# SDLbeerlight0.net
KiCad netlist of a schematic drawn in EAGLE
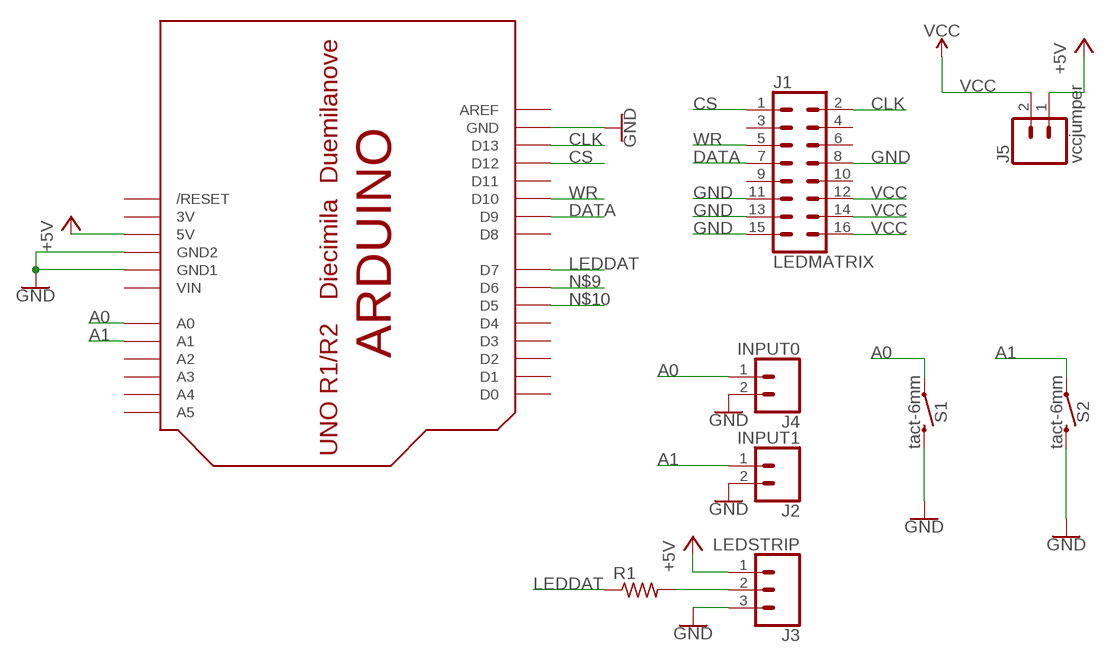
[diagram p0: schematic, sheet 1]

(export (version "E")
  (design (tool "Eeschema 10.0.6"))
  (components
    (comp (ref "J1")
      (value "LEDMATRIX")
      (footprint "eagle-import:2X8")
      (libsource (lib "eagle-import") (part "CONN_08X2"))
    )
    (comp (ref "J2")
      (value "INPUT1")
      (footprint "eagle-import:1X02_LONGPADS")
      (libsource (lib "eagle-import") (part "CONN_02PTH3"))
    )
    (comp (ref "J3")
      (value "LEDSTRIP")
      (footprint "eagle-import:1X03_LONGPADS")
      (libsource (lib "eagle-import") (part "CONN_03LONGPADS"))
    )
    (comp (ref "J4")
      (value "INPUT0")
      (footprint "eagle-import:1X02_LONGPADS")
      (libsource (lib "eagle-import") (part "CONN_02PTH3"))
    )
    (comp (ref "J5")
      (value "vccjumper")
      (footprint "eagle-import:1X02_LOCK_LONGPADS")
      (libsource (lib "eagle-import") (part "CONN_02LOCK_LONGPADS"))
    )
    (comp (ref "R1")
      (value "R-US_M0805")
      (footprint "eagle-import:M0805")
      (libsource (lib "eagle-import") (part "R-US_M0805"))
    )
    (comp (ref "S1")
      (value "tact-6mm")
      (footprint "eagle-import:TACTILE_SWITCH_PTH_6.0MM")
      (libsource (lib "eagle-import") (part "MOMENTARY-SWITCH-SPST-PTH-6.0MM"))
    )
    (comp (ref "S2")
      (value "tact-6mm")
      (footprint "eagle-import:TACTILE_SWITCH_PTH_6.0MM")
      (libsource (lib "eagle-import") (part "MOMENTARY-SWITCH-SPST-PTH-6.0MM"))
    )
    (comp (ref "U$2")
      (value "ARDUINOUNO")
      (footprint "eagle-import:ARDUINO")
      (libsource (lib "eagle-import") (part "ARDUINOUNO"))
    )
  )
  (nets
    (net (code "1") (name "+5V") (class "Default")
      (node (ref "J3") (pin "1") (pinfunction "1_1") (pintype "passive"))
      (node (ref "J5") (pin "1") (pinfunction "1_1") (pintype "passive"))
      (node (ref "U$2") (pin "5V") (pinfunction "5V_5V") (pintype "power_in"))
    )
    (net (code "2") (name "/3V") (class "Default")
      (node (ref "U$2") (pin "3V") (pinfunction "3V_3V") (pintype "power_in"))
    )
    (net (code "3") (name "/A0") (class "Default")
      (node (ref "J4") (pin "1") (pinfunction "1_1") (pintype "passive"))
      (node (ref "S1") (pin "1") (pinfunction "1_1") (pintype "passive"))
      (node (ref "U$2") (pin "A0") (pinfunction "A0_A0") (pintype "bidirectional"))
    )
    (net (code "4") (name "/A1") (class "Default")
      (node (ref "J2") (pin "1") (pinfunction "1_1") (pintype "passive"))
      (node (ref "S2") (pin "1") (pinfunction "1_1") (pintype "passive"))
      (node (ref "U$2") (pin "A1") (pinfunction "A1_A1") (pintype "bidirectional"))
    )
    (net (code "5") (name "/CLK") (class "Default")
      (node (ref "J1") (pin "2") (pinfunction "2_2") (pintype "passive"))
      (node (ref "U$2") (pin "D13") (pinfunction "D13_D13") (pintype "bidirectional"))
    )
    (net (code "6") (name "/CS") (class "Default")
      (node (ref "J1") (pin "1") (pinfunction "1_1") (pintype "passive"))
      (node (ref "U$2") (pin "D12") (pinfunction "D12_D12") (pintype "bidirectional"))
    )
    (net (code "7") (name "/DATA") (class "Default")
      (node (ref "J1") (pin "7") (pinfunction "7_7") (pintype "passive"))
      (node (ref "U$2") (pin "D9") (pinfunction "D9_D9") (pintype "bidirectional"))
    )
    (net (code "8") (name "/LEDDAT") (class "Default")
      (node (ref "R1") (pin "1") (pinfunction "1_1") (pintype "passive"))
      (node (ref "U$2") (pin "D7") (pinfunction "D7_D7") (pintype "bidirectional"))
    )
    (net (code "9") (name "/N$9") (class "Default")
      (node (ref "U$2") (pin "D6") (pinfunction "D6_D6") (pintype "bidirectional"))
    )
    (net (code "10") (name "/N$10") (class "Default")
      (node (ref "U$2") (pin "D5") (pinfunction "D5_D5") (pintype "bidirectional"))
    )
    (net (code "11") (name "/VIN") (class "Default")
      (node (ref "U$2") (pin "VIN") (pinfunction "VIN_VIN") (pintype "power_in"))
    )
    (net (code "12") (name "/WR") (class "Default")
      (node (ref "J1") (pin "5") (pinfunction "5_5") (pintype "passive"))
      (node (ref "U$2") (pin "D10") (pinfunction "D10_D10") (pintype "bidirectional"))
    )
    (net (code "13") (name "GND") (class "Default")
      (node (ref "J1") (pin "11") (pinfunction "11_11") (pintype "passive"))
      (node (ref "J1") (pin "13") (pinfunction "13_13") (pintype "passive"))
      (node (ref "J1") (pin "15") (pinfunction "15_15") (pintype "passive"))
      (node (ref "J1") (pin "8") (pinfunction "8_8") (pintype "passive"))
      (node (ref "J2") (pin "2") (pinfunction "2_2") (pintype "passive"))
      (node (ref "J3") (pin "3") (pinfunction "3_3") (pintype "passive"))
      (node (ref "J4") (pin "2") (pinfunction "2_2") (pintype "passive"))
      (node (ref "S1") (pin "3") (pinfunction "2_3") (pintype "passive"))
      (node (ref "S2") (pin "3") (pinfunction "2_3") (pintype "passive"))
      (node (ref "U$2") (pin "GND") (pinfunction "GND_GND") (pintype "power_in"))
      (node (ref "U$2") (pin "GND1") (pinfunction "GND1_GND1") (pintype "power_in"))
      (node (ref "U$2") (pin "GND2") (pinfunction "GND2_GND2") (pintype "power_in"))
    )
    (net (code "14") (name "Net-(J3-Pad2)") (class "Default")
      (node (ref "J3") (pin "2") (pinfunction "2_2") (pintype "passive"))
      (node (ref "R1") (pin "2") (pinfunction "2_2") (pintype "passive"))
    )
    (net (code "15") (name "VCC") (class "Default")
      (node (ref "J1") (pin "12") (pinfunction "12_12") (pintype "passive"))
      (node (ref "J1") (pin "14") (pinfunction "14_14") (pintype "passive"))
      (node (ref "J1") (pin "16") (pinfunction "16_16") (pintype "passive"))
      (node (ref "J5") (pin "2") (pinfunction "2_2") (pintype "passive"))
    )
    (net (code "16") (name "unconnected-(J1-Pad3)") (class "Default")
      (node (ref "J1") (pin "3") (pinfunction "3_3") (pintype "passive"))
    )
    (net (code "17") (name "unconnected-(J1-Pad4)") (class "Default")
      (node (ref "J1") (pin "4") (pinfunction "4_4") (pintype "passive"))
    )
    (net (code "18") (name "unconnected-(J1-Pad6)") (class "Default")
      (node (ref "J1") (pin "6") (pinfunction "6_6") (pintype "passive"))
    )
    (net (code "19") (name "unconnected-(J1-Pad9)") (class "Default")
      (node (ref "J1") (pin "9") (pinfunction "9_9") (pintype "passive"))
    )
    (net (code "20") (name "unconnected-(J1-Pad10)") (class "Default")
      (node (ref "J1") (pin "10") (pinfunction "10_10") (pintype "passive"))
    )
    (net (code "21") (name "unconnected-(U$2-PadA2)") (class "Default")
      (node (ref "U$2") (pin "A2") (pinfunction "A2_A2") (pintype "bidirectional"))
    )
    (net (code "22") (name "unconnected-(U$2-PadA3)") (class "Default")
      (node (ref "U$2") (pin "A3") (pinfunction "A3_A3") (pintype "bidirectional"))
    )
    (net (code "23") (name "unconnected-(U$2-PadA4)") (class "Default")
      (node (ref "U$2") (pin "A4") (pinfunction "A4_A4") (pintype "bidirectional"))
    )
    (net (code "24") (name "unconnected-(U$2-PadA5)") (class "Default")
      (node (ref "U$2") (pin "A5") (pinfunction "A5_A5") (pintype "bidirectional"))
    )
    (net (code "25") (name "unconnected-(U$2-PadAREF)") (class "Default")
      (node (ref "U$2") (pin "AREF") (pinfunction "AREF_AREF") (pintype "bidirectional"))
    )
    (net (code "26") (name "unconnected-(U$2-PadD0)") (class "Default")
      (node (ref "U$2") (pin "D0") (pinfunction "D0_D0") (pintype "bidirectional"))
    )
    (net (code "27") (name "unconnected-(U$2-PadD1)") (class "Default")
      (node (ref "U$2") (pin "D1") (pinfunction "D1_D1") (pintype "bidirectional"))
    )
    (net (code "28") (name "unconnected-(U$2-PadD2)") (class "Default")
      (node (ref "U$2") (pin "D2") (pinfunction "D2_D2") (pintype "bidirectional"))
    )
    (net (code "29") (name "unconnected-(U$2-PadD3)") (class "Default")
      (node (ref "U$2") (pin "D3") (pinfunction "D3_D3") (pintype "bidirectional"))
    )
    (net (code "30") (name "unconnected-(U$2-PadD4)") (class "Default")
      (node (ref "U$2") (pin "D4") (pinfunction "D4_D4") (pintype "bidirectional"))
    )
    (net (code "31") (name "unconnected-(U$2-PadD8)") (class "Default")
      (node (ref "U$2") (pin "D8") (pinfunction "D8_D8") (pintype "bidirectional"))
    )
    (net (code "32") (name "unconnected-(U$2-PadD11)") (class "Default")
      (node (ref "U$2") (pin "D11") (pinfunction "D11_D11") (pintype "bidirectional"))
    )
    (net (code "33") (name "unconnected-(U$2-{slash}RESET-PadRESET)") (class "Default")
      (node (ref "U$2") (pin "RESET") (pinfunction "/RESET_RESET") (pintype "bidirectional"))
    )
  )
)
